# SunBoost.net
KiCad netlist of a schematic drawn in Altium Designer
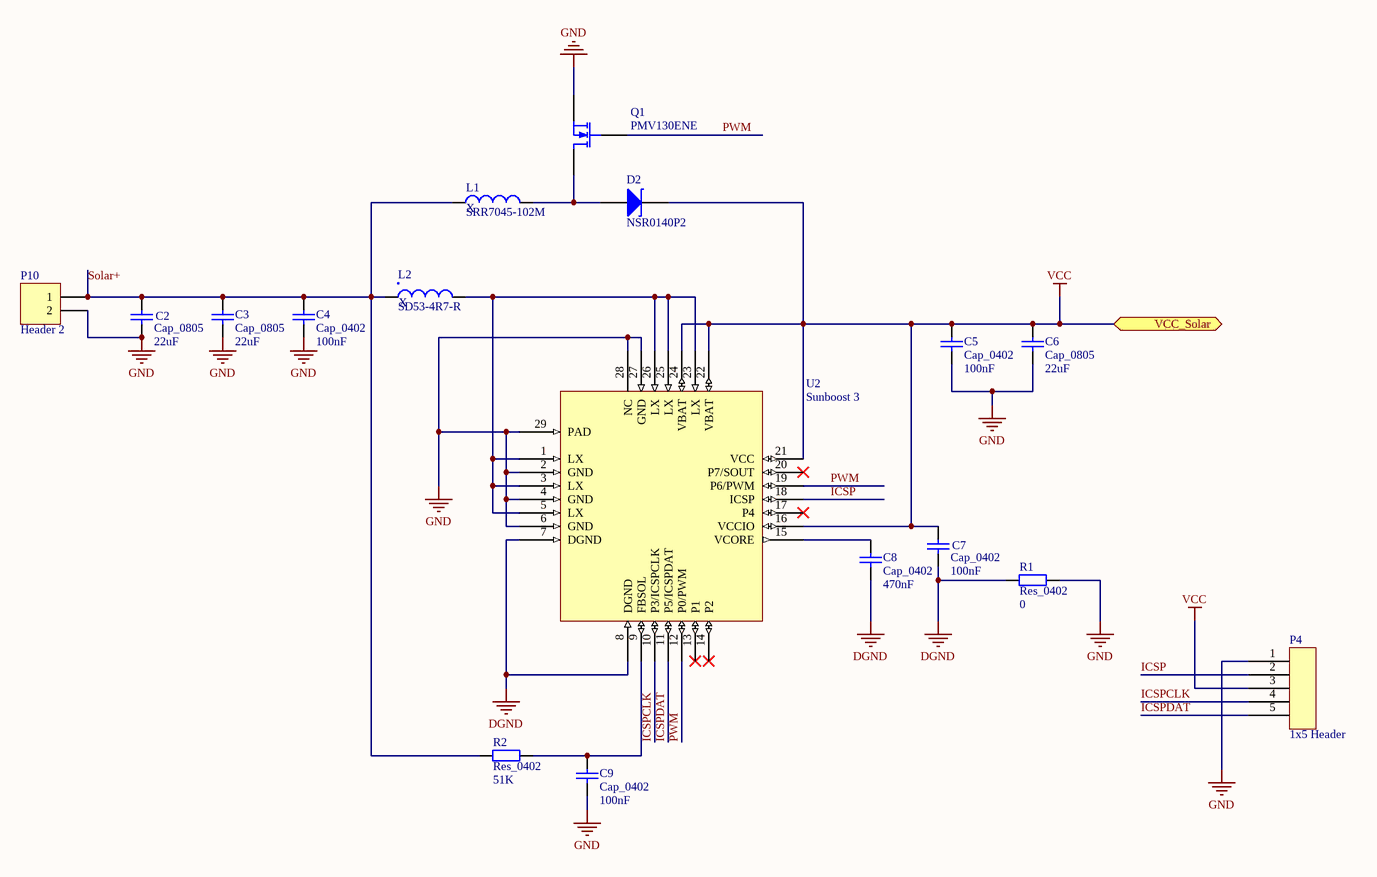
[diagram p0: SunBoost.SchDoc]

(export (version "E")
  (design (tool "Eeschema 10.0.6"))
  (components
    (comp (ref "C2")
      (value "Cap_0805")
      (footprint "0805")
      (description "Capacitor")
      (fields (field (name "ALTIUM_VALUE") "22uF") (field (name "PUBLISHER") "Altium Limited"))
      (libsource (lib "Schematic_Components") (part "Cap_0805"))
    )
    (comp (ref "C3")
      (value "Cap_0805")
      (footprint "0805")
      (description "Capacitor")
      (fields (field (name "ALTIUM_VALUE") "22uF") (field (name "PUBLISHER") "Altium Limited"))
      (libsource (lib "Schematic_Components") (part "Cap_0805"))
    )
    (comp (ref "C4")
      (value "Cap_0402")
      (footprint "0402")
      (description "Capacitor")
      (fields (field (name "ALTIUM_VALUE") "100nF") (field (name "PUBLISHER") "Altium Limited"))
      (libsource (lib "Schematic_Components") (part "Cap_0402"))
    )
    (comp (ref "C5")
      (value "Cap_0402")
      (footprint "0402")
      (description "Capacitor")
      (fields (field (name "ALTIUM_VALUE") "100nF") (field (name "PUBLISHER") "Altium Limited"))
      (libsource (lib "Schematic_Components") (part "Cap_0402"))
    )
    (comp (ref "C6")
      (value "Cap_0805")
      (footprint "0805")
      (description "Capacitor")
      (fields (field (name "ALTIUM_VALUE") "22uF") (field (name "PUBLISHER") "Altium Limited"))
      (libsource (lib "Schematic_Components") (part "Cap_0805"))
    )
    (comp (ref "C7")
      (value "Cap_0402")
      (footprint "0402")
      (description "Capacitor")
      (fields (field (name "ALTIUM_VALUE") "100nF") (field (name "PUBLISHER") "Altium Limited"))
      (libsource (lib "Schematic_Components") (part "Cap_0402"))
    )
    (comp (ref "C8")
      (value "Cap_0402")
      (footprint "0402")
      (description "Capacitor")
      (fields (field (name "ALTIUM_VALUE") "470nF") (field (name "PUBLISHER") "Altium Limited"))
      (libsource (lib "Schematic_Components") (part "Cap_0402"))
    )
    (comp (ref "C9")
      (value "Cap_0402")
      (footprint "0402")
      (description "Capacitor")
      (fields (field (name "ALTIUM_VALUE") "100nF") (field (name "PUBLISHER") "Altium Limited"))
      (libsource (lib "Schematic_Components") (part "Cap_0402"))
    )
    (comp (ref "D2")
      (value "NSR0140P2")
      (footprint "SOD-923")
      (description "Typical INFRARED GaAs LED")
      (fields (field (name "PUBLISHER") "Altium Limited"))
      (libsource (lib "Schematic_Components") (part "NSR0140P2"))
    )
    (comp (ref "L1")
      (value "SRR7045-102M")
      (footprint "SRR7045-102M")
      (description "Inductor")
      (fields (field (name "ALTIUM_VALUE") "X"))
      (libsource (lib "Schematic_Components") (part "SRR7045-102M"))
    )
    (comp (ref "L2")
      (value "SD53-4R7-R")
      (footprint "SD53-4R7-R")
      (description "Inductor")
      (fields (field (name "ALTIUM_VALUE") "X"))
      (libsource (lib "Schematic_Components") (part "SD53-4R7-R"))
    )
    (comp (ref "P4")
      (value "1x5 Header")
      (footprint "1x5 Header 1.27")
      (libsource (lib "Schematic_Components") (part "1x5 Header"))
    )
    (comp (ref "P10")
      (value "Header 2")
      (footprint "HDR1X2")
      (description "Header, 2-Pin")
      (fields (field (name "PUBLISHER") "Altium Limited"))
      (libsource (lib "Miscellaneous Connectors") (part "Header 2"))
    )
    (comp (ref "Q1")
      (value "PMV130ENE")
      (footprint "SOT-23")
      (description "N-Channel MOSFET")
      (fields (field (name "PUBLISHER") "Altium Limited"))
      (libsource (lib "Schematic_Components") (part "PMV130ENE"))
    )
    (comp (ref "R1")
      (value "Res_0402")
      (footprint "0402")
      (description "Resistor")
      (fields (field (name "ALTIUM_VALUE") "0") (field (name "PUBLISHER") "Altium Limited"))
      (libsource (lib "Schematic_Components") (part "Res_0402"))
    )
    (comp (ref "R2")
      (value "Res_0402")
      (footprint "0402")
      (description "Resistor")
      (fields (field (name "ALTIUM_VALUE") "51K") (field (name "PUBLISHER") "Altium Limited"))
      (libsource (lib "Schematic_Components") (part "Res_0402"))
    )
    (comp (ref "U2")
      (value "Sunboost 3")
      (footprint "28-QFN_0.4mm")
      (description "Initvation Sunboost 3")
      (libsource (lib "Schematic_Components") (part "Sunboost 3"))
    )
  )
  (nets
    (net (code "1") (name "/ICSP") (class "Default")
      (node (ref "P4") (pin "2") (pintype "passive"))
      (node (ref "U2") (pin "18") (pinfunction "ICSP_18") (pintype "bidirectional"))
    )
    (net (code "2") (name "/ICSPCLK") (class "Default")
      (node (ref "P4") (pin "4") (pintype "passive"))
      (node (ref "U2") (pin "10") (pinfunction "P3/ICSPCLK_10") (pintype "bidirectional"))
    )
    (net (code "3") (name "/ICSPDAT") (class "Default")
      (node (ref "P4") (pin "5") (pintype "passive"))
      (node (ref "U2") (pin "11") (pinfunction "P5/ICSPDAT_11") (pintype "bidirectional"))
    )
    (net (code "4") (name "/PWM") (class "Default")
      (node (ref "Q1") (pin "1") (pinfunction "G_1") (pintype "passive"))
      (node (ref "U2") (pin "12") (pinfunction "P0/PWM_12") (pintype "bidirectional"))
      (node (ref "U2") (pin "19") (pinfunction "P6/PWM_19") (pintype "bidirectional"))
    )
    (net (code "5") (name "/Solar+") (class "Default")
      (node (ref "C2") (pin "2") (pinfunction "2_2") (pintype "passive"))
      (node (ref "C3") (pin "2") (pinfunction "2_2") (pintype "passive"))
      (node (ref "C4") (pin "2") (pinfunction "2_2") (pintype "passive"))
      (node (ref "L1") (pin "1") (pinfunction "1_1") (pintype "passive"))
      (node (ref "L2") (pin "1") (pinfunction "1_1") (pintype "passive"))
      (node (ref "P10") (pin "1") (pinfunction "1_1") (pintype "passive"))
      (node (ref "R2") (pin "1") (pinfunction "1_1") (pintype "passive"))
    )
    (net (code "6") (name "DGND") (class "Default")
      (node (ref "C7") (pin "1") (pinfunction "1_1") (pintype "passive"))
      (node (ref "C8") (pin "1") (pinfunction "1_1") (pintype "passive"))
      (node (ref "R1") (pin "1") (pinfunction "1_1") (pintype "passive"))
      (node (ref "U2") (pin "7") (pinfunction "DGND_7") (pintype "input"))
      (node (ref "U2") (pin "8") (pinfunction "DGND_8") (pintype "input"))
    )
    (net (code "7") (name "GND") (class "Default")
      (node (ref "C2") (pin "1") (pinfunction "1_1") (pintype "passive"))
      (node (ref "C3") (pin "1") (pinfunction "1_1") (pintype "passive"))
      (node (ref "C4") (pin "1") (pinfunction "1_1") (pintype "passive"))
      (node (ref "C5") (pin "1") (pinfunction "1_1") (pintype "passive"))
      (node (ref "C6") (pin "1") (pinfunction "1_1") (pintype "passive"))
      (node (ref "C9") (pin "1") (pinfunction "1_1") (pintype "passive"))
      (node (ref "P10") (pin "2") (pinfunction "2_2") (pintype "passive"))
      (node (ref "P4") (pin "1") (pintype "passive"))
      (node (ref "Q1") (pin "2") (pinfunction "S_2") (pintype "passive"))
      (node (ref "R1") (pin "2") (pinfunction "2_2") (pintype "passive"))
      (node (ref "U2") (pin "2") (pinfunction "GND_2") (pintype "input"))
      (node (ref "U2") (pin "27") (pinfunction "GND_27") (pintype "input"))
      (node (ref "U2") (pin "28") (pinfunction "NC_28") (pintype "passive"))
      (node (ref "U2") (pin "29") (pinfunction "PAD_29") (pintype "input"))
      (node (ref "U2") (pin "4") (pinfunction "GND_4") (pintype "input"))
      (node (ref "U2") (pin "6") (pinfunction "GND_6") (pintype "input"))
    )
    (net (code "8") (name "Net-(D2-A)") (class "Default")
      (node (ref "D2") (pin "2") (pinfunction "A_2") (pintype "passive"))
      (node (ref "L1") (pin "2") (pinfunction "2_2") (pintype "passive"))
      (node (ref "Q1") (pin "3") (pinfunction "D_3") (pintype "passive"))
    )
    (net (code "9") (name "Net-(L2-Pad2)") (class "Default")
      (node (ref "L2") (pin "2") (pinfunction "2_2") (pintype "passive"))
      (node (ref "U2") (pin "1") (pinfunction "LX_1") (pintype "input"))
      (node (ref "U2") (pin "23") (pinfunction "LX_23") (pintype "input"))
      (node (ref "U2") (pin "25") (pinfunction "LX_25") (pintype "input"))
      (node (ref "U2") (pin "26") (pinfunction "LX_26") (pintype "input"))
      (node (ref "U2") (pin "3") (pinfunction "LX_3") (pintype "input"))
      (node (ref "U2") (pin "5") (pinfunction "LX_5") (pintype "input"))
    )
    (net (code "10") (name "Net-(U2-FBSOL)") (class "Default")
      (node (ref "C9") (pin "2") (pinfunction "2_2") (pintype "passive"))
      (node (ref "R2") (pin "2") (pinfunction "2_2") (pintype "passive"))
      (node (ref "U2") (pin "9") (pinfunction "FBSOL_9") (pintype "bidirectional"))
    )
    (net (code "11") (name "Net-(U2-VCORE)") (class "Default")
      (node (ref "C8") (pin "2") (pinfunction "2_2") (pintype "passive"))
      (node (ref "U2") (pin "15") (pinfunction "VCORE_15") (pintype "output"))
    )
    (net (code "12") (name "VCC") (class "Default")
      (node (ref "C5") (pin "2") (pinfunction "2_2") (pintype "passive"))
      (node (ref "C6") (pin "2") (pinfunction "2_2") (pintype "passive"))
      (node (ref "C7") (pin "2") (pinfunction "2_2") (pintype "passive"))
      (node (ref "D2") (pin "1") (pinfunction "K_1") (pintype "passive"))
      (node (ref "P4") (pin "3") (pintype "passive"))
      (node (ref "U2") (pin "16") (pinfunction "VCCIO_16") (pintype "bidirectional"))
      (node (ref "U2") (pin "21") (pinfunction "VCC_21") (pintype "bidirectional"))
      (node (ref "U2") (pin "22") (pinfunction "VBAT_22") (pintype "bidirectional"))
      (node (ref "U2") (pin "24") (pinfunction "VBAT_24") (pintype "bidirectional"))
    )
    (net (code "13") (name "unconnected-(U2-P1-Pad13)") (class "Default")
      (node (ref "U2") (pin "13") (pinfunction "P1_13") (pintype "bidirectional+no_connect"))
    )
    (net (code "14") (name "unconnected-(U2-P2-Pad14)") (class "Default")
      (node (ref "U2") (pin "14") (pinfunction "P2_14") (pintype "bidirectional+no_connect"))
    )
    (net (code "15") (name "unconnected-(U2-P4-Pad17)") (class "Default")
      (node (ref "U2") (pin "17") (pinfunction "P4_17") (pintype "bidirectional+no_connect"))
    )
    (net (code "16") (name "unconnected-(U2-P7{slash}SOUT-Pad20)") (class "Default")
      (node (ref "U2") (pin "20") (pinfunction "P7/SOUT_20") (pintype "bidirectional+no_connect"))
    )
  )
)
